# Ele1.net
KiCad netlist of a schematic drawn in EAGLE
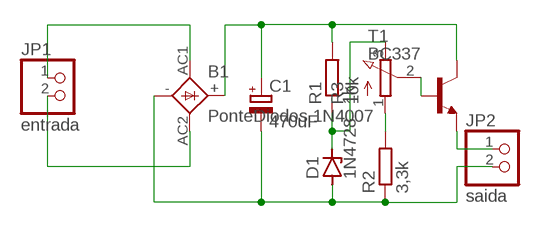
[diagram p0: schematic, sheet 1]

(export (version "E")
  (design (tool "Eeschema 10.0.6"))
  (components
    (comp (ref "B1")
      (value "PonteDiodos 1N4007")
      (footprint "eagle-import:1KAB")
      (libsource (lib "eagle-import") (part "1KAB"))
    )
    (comp (ref "C1")
      (value "470uF")
      (footprint "eagle-import:E5-10,5")
      (libsource (lib "eagle-import") (part "CPOL-EUE5-10.5"))
    )
    (comp (ref "D1")
      (value "1N4728")
      (footprint "eagle-import:DO41Z10")
      (libsource (lib "eagle-import") (part "1N4728"))
    )
    (comp (ref "JP1")
      (value "entrada")
      (footprint "eagle-import:1X02")
      (libsource (lib "eagle-import") (part "PINHD-1X2"))
    )
    (comp (ref "JP2")
      (value "saida")
      (footprint "eagle-import:1X02")
      (libsource (lib "eagle-import") (part "PINHD-1X2"))
    )
    (comp (ref "R1")
      (value "1k")
      (footprint "eagle-import:0204_7")
      (libsource (lib "eagle-import") (part "R-EU_0204/7"))
    )
    (comp (ref "R2")
      (value "3,3k")
      (footprint "eagle-import:0204_7")
      (libsource (lib "eagle-import") (part "R-EU_0204/7"))
    )
    (comp (ref "R3")
      (value "10k")
      (footprint "eagle-import:3RP_1610N")
      (libsource (lib "eagle-import") (part "3RP/1610N"))
    )
    (comp (ref "T1")
      (value "BC337")
      (footprint "eagle-import:TO92")
      (libsource (lib "eagle-import") (part "2N3904"))
    )
  )
  (nets
    (net (code "1") (name "Net-(B1-Pad-)") (class "Default")
      (node (ref "B1") (pin "-") (pinfunction "-_-") (pintype "passive"))
      (node (ref "C1") (pin "-") (pinfunction "-_-") (pintype "passive"))
      (node (ref "D1") (pin "A") (pinfunction "A_A") (pintype "passive"))
      (node (ref "JP2") (pin "2") (pinfunction "2_2") (pintype "passive"))
      (node (ref "R2") (pin "1") (pinfunction "1_1") (pintype "passive"))
    )
    (net (code "2") (name "Net-(B1-PadAC1)") (class "Default")
      (node (ref "B1") (pin "AC1") (pinfunction "AC1_AC1") (pintype "passive"))
      (node (ref "JP1") (pin "1") (pinfunction "1_1") (pintype "passive"))
    )
    (net (code "3") (name "Net-(B1-PadAC2)") (class "Default")
      (node (ref "B1") (pin "AC2") (pinfunction "AC2_AC2") (pintype "passive"))
      (node (ref "JP1") (pin "2") (pinfunction "2_2") (pintype "passive"))
    )
    (net (code "4") (name "Net-(R3-A)") (class "Default")
      (node (ref "R2") (pin "2") (pinfunction "2_2") (pintype "passive"))
      (node (ref "R3") (pin "1") (pinfunction "A_1") (pintype "passive"))
    )
    (net (code "5") (name "Net-(R3-E)") (class "Default")
      (node (ref "D1") (pin "C") (pinfunction "C_C") (pintype "passive"))
      (node (ref "R1") (pin "1") (pinfunction "1_1") (pintype "passive"))
      (node (ref "R3") (pin "3") (pinfunction "E_3") (pintype "passive"))
    )
    (net (code "6") (name "Net-(R3-S)") (class "Default")
      (node (ref "R3") (pin "2") (pinfunction "S_2") (pintype "passive"))
      (node (ref "T1") (pin "2") (pinfunction "B_2") (pintype "passive"))
    )
    (net (code "7") (name "Net-(T1-C)") (class "Default")
      (node (ref "B1") (pin "+") (pinfunction "+_+") (pintype "passive"))
      (node (ref "C1") (pin "+") (pinfunction "+_+") (pintype "passive"))
      (node (ref "R1") (pin "2") (pinfunction "2_2") (pintype "passive"))
      (node (ref "T1") (pin "1") (pinfunction "C_1") (pintype "passive"))
    )
    (net (code "8") (name "Net-(T1-E)") (class "Default")
      (node (ref "JP2") (pin "1") (pinfunction "1_1") (pintype "passive"))
      (node (ref "T1") (pin "3") (pinfunction "E_3") (pintype "passive"))
    )
  )
)
